# ppmacBoard.net
KiCad netlist of a schematic drawn in EAGLE
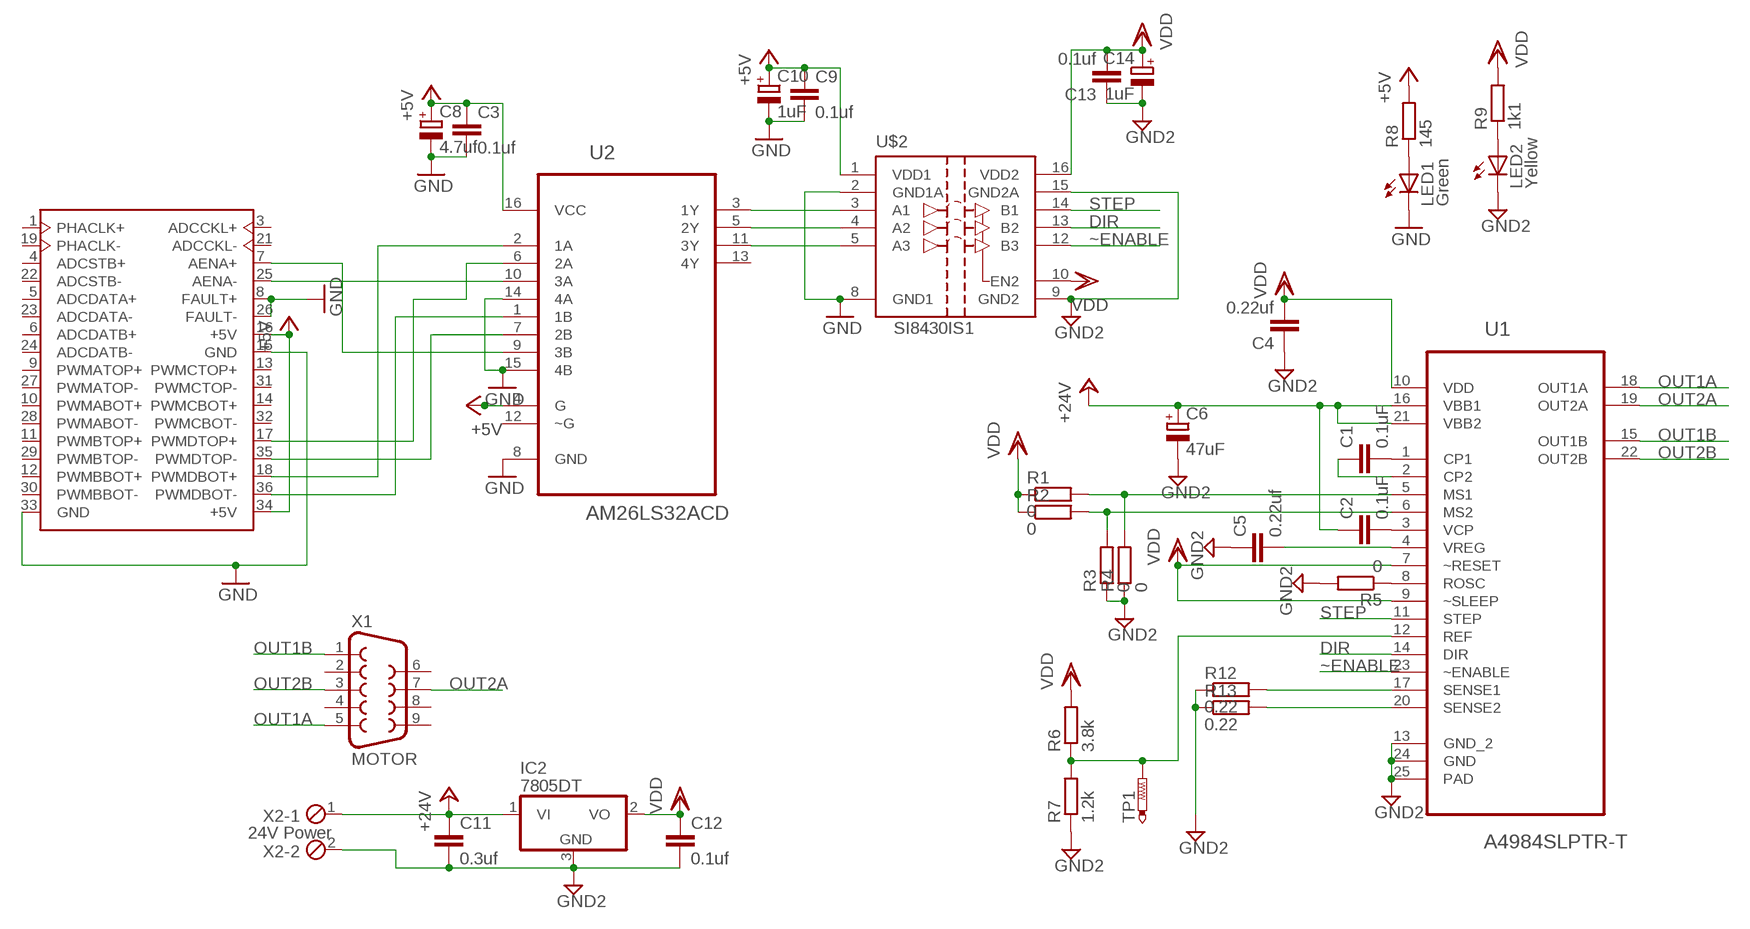
[diagram p0: schematic, sheet 1]

(export (version "E")
  (design (tool "Eeschema 10.0.6"))
  (components
    (comp (ref "C1")
      (value "0.1uF")
      (footprint "eagle-import:C1206")
      (fields (field (name "MPN") "MC1206B104K250CT") (field (name "PARTNO") "C1206C104K3RACTU"))
      (libsource (lib "eagle-import") (part "C-EUC1206"))
    )
    (comp (ref "C2")
      (value "0.1uF")
      (footprint "eagle-import:C1206")
      (fields (field (name "MPN") "MC1206B104K250CT") (field (name "PARTNO") "C1206C104K3RACTU"))
      (libsource (lib "eagle-import") (part "C-EUC1206"))
    )
    (comp (ref "C3")
      (value "0.1uf")
      (footprint "eagle-import:C1206")
      (fields (field (name "PARTNO") "C1206C104K3RACTU"))
      (libsource (lib "eagle-import") (part "C-EUC1206"))
    )
    (comp (ref "C4")
      (value "0.22uf")
      (footprint "eagle-import:C1206")
      (fields (field (name "PARTNO") "C1206C224K5RACTU"))
      (libsource (lib "eagle-import") (part "C-EUC1206"))
    )
    (comp (ref "C5")
      (value "0.22uf")
      (footprint "eagle-import:C1206")
      (fields (field (name "PARTNO") "C1206C224K5RACTU"))
      (libsource (lib "eagle-import") (part "C-EUC1206"))
    )
    (comp (ref "C6")
      (value "47uF")
      (footprint "eagle-import:E7,5-18")
      (fields (field (name "PARTNO") "ESH476M035AE3AA"))
      (libsource (lib "eagle-import") (part "CPOL-EUE7.5-18"))
    )
    (comp (ref "C8")
      (value "4.7uf")
      (footprint "eagle-import:A_3216-18W")
      (fields (field (name "PARTNO") "T491A475M025AT"))
      (libsource (lib "eagle-import") (part "CPOL-EUA/3216-18W"))
    )
    (comp (ref "C9")
      (value "0.1uf")
      (footprint "eagle-import:C1206")
      (fields (field (name "PARTNO") "C1206C104K3RACTU"))
      (libsource (lib "eagle-import") (part "C-EUC1206"))
    )
    (comp (ref "C10")
      (value "1uF")
      (footprint "eagle-import:A_3216-18W")
      (fields (field (name "PARTNO") "T491A105K025AT"))
      (libsource (lib "eagle-import") (part "CPOL-EUA/3216-18W"))
    )
    (comp (ref "C11")
      (value "0.3uf")
      (footprint "eagle-import:C1206")
      (fields (field (name "PARTNO") "C3216X7R1E334K"))
      (libsource (lib "eagle-import") (part "C-EUC1206"))
    )
    (comp (ref "C12")
      (value "0.1uf")
      (footprint "eagle-import:C1206")
      (fields (field (name "PARTNO") "C1206C104K3RACTU"))
      (libsource (lib "eagle-import") (part "C-EUC1206"))
    )
    (comp (ref "C13")
      (value "0.1uf")
      (footprint "eagle-import:C1206")
      (fields (field (name "PARTNO") "C1206C104K3RACTU"))
      (libsource (lib "eagle-import") (part "C-EUC1206"))
    )
    (comp (ref "C14")
      (value "1uF")
      (footprint "eagle-import:A_3216-18W")
      (fields (field (name "PARTNO") "T491A105K025AT"))
      (libsource (lib "eagle-import") (part "CPOL-EUA/3216-18W"))
    )
    (comp (ref "IC2")
      (value "7805DT")
      (footprint "eagle-import:TO252")
      (fields (field (name "PARTNO") "BA17805FP-E2"))
      (libsource (lib "eagle-import") (part "78DT05"))
    )
    (comp (ref "LED1")
      (value "Green")
      (footprint "eagle-import:1206")
      (fields (field (name "MPN") "KP-3216CGCK") (field (name "PARTNO") "LG N971-KN-1"))
      (libsource (lib "eagle-import") (part "LEDSMT1206"))
    )
    (comp (ref "LED2")
      (value "Yellow")
      (footprint "eagle-import:1206")
      (fields (field (name "MPN") "KP-3216SYCK") (field (name "PARTNO") "APT3216YC"))
      (libsource (lib "eagle-import") (part "LEDSMT1206"))
    )
    (comp (ref "R1")
      (value "0")
      (footprint "eagle-import:R1206")
      (fields (field (name "PARTNO") "RMCF1206ZT0R00"))
      (libsource (lib "eagle-import") (part "R-EU_R1206"))
    )
    (comp (ref "R2")
      (value "0")
      (footprint "eagle-import:R1206")
      (fields (field (name "PARTNO") "RMCF1206ZT0R00"))
      (libsource (lib "eagle-import") (part "R-EU_R1206"))
    )
    (comp (ref "R3")
      (value "0")
      (footprint "eagle-import:R1206")
      (fields (field (name "PARTNO") "RMCF1206ZT0R00"))
      (libsource (lib "eagle-import") (part "R-EU_R1206"))
    )
    (comp (ref "R4")
      (value "0")
      (footprint "eagle-import:R1206")
      (fields (field (name "PARTNO") "RMCF1206ZT0R00"))
      (libsource (lib "eagle-import") (part "R-EU_R1206"))
    )
    (comp (ref "R5")
      (value "0")
      (footprint "eagle-import:R1206")
      (fields (field (name "PARTNO") "RMCF1206ZT0R00"))
      (libsource (lib "eagle-import") (part "R-EU_R1206"))
    )
    (comp (ref "R6")
      (value "3.8k")
      (footprint "eagle-import:R1206")
      (fields (field (name "PARTNO") "RMCF1206FT3K83"))
      (libsource (lib "eagle-import") (part "R-EU_R1206"))
    )
    (comp (ref "R7")
      (value "1.2k")
      (footprint "eagle-import:R1206")
      (fields (field (name "PARTNO") "RC1206FR-071K2L"))
      (libsource (lib "eagle-import") (part "R-EU_R1206"))
    )
    (comp (ref "R8")
      (value "145")
      (footprint "eagle-import:R1206")
      (fields (field (name "PARTNO") "RC1206FR-07140RL"))
      (libsource (lib "eagle-import") (part "R-EU_R1206"))
    )
    (comp (ref "R9")
      (value "1k1")
      (footprint "eagle-import:R1206")
      (fields (field (name "PARTNO") "RC1206FR-071K1L"))
      (libsource (lib "eagle-import") (part "R-EU_R1206"))
    )
    (comp (ref "R12")
      (value "0.22")
      (footprint "eagle-import:R2010")
      (fields (field (name "PARTNO") "WSLT2010R2200FEB18"))
      (libsource (lib "eagle-import") (part "R-EU_R2010"))
    )
    (comp (ref "R13")
      (value "0.22")
      (footprint "eagle-import:R2010")
      (fields (field (name "PARTNO") "WSLT2010R2200FEB18"))
      (libsource (lib "eagle-import") (part "R-EU_R2010"))
    )
    (comp (ref "TP1")
      (value "PTR1PAD1-13")
      (footprint "eagle-import:P1-13")
      (libsource (lib "eagle-import") (part "PTR1PAD1-13"))
    )
    (comp (ref "U$1")
      (value "DIGAMPOUT_PCB")
      (footprint "eagle-import:3M_10136-52B2PC_PCB")
      (fields (field (name "PARTNO") "10136-3000PE"))
      (libsource (lib "eagle-import") (part "DIGAMPOUT_PCB"))
    )
    (comp (ref "U$2")
      (value "SI8430IS1")
      (footprint "eagle-import:SO16")
      (fields (field (name "PARTNO") "SI8430AB-D-IS1"))
      (libsource (lib "eagle-import") (part "SI8430IS1"))
    )
    (comp (ref "U1")
      (value "A4984SLPTR-T")
      (footprint "eagle-import:SOP65P640X120-24N")
      (libsource (lib "eagle-import") (part "A4984SLPTR-T"))
    )
    (comp (ref "U2")
      (value "AM26LS32ACD")
      (footprint "eagle-import:SOIC127P600X175-16N")
      (fields (field (name "MF") "TEXAS INSTRUMENTS") (field (name "PARTNO") "AM26LS32ACDR"))
      (libsource (lib "eagle-import") (part "AM26LS32ACD"))
    )
    (comp (ref "X1")
      (value "MOTOR")
      (footprint "eagle-import:F09H")
      (fields (field (name "PARTNO") "DLS1XS5AK40X"))
      (libsource (lib "eagle-import") (part "F09H"))
    )
    (comp (ref "X2")
      (value "24V Power")
      (footprint "eagle-import:2POL254")
      (fields (field (name "PARTNO") "OSTTE020104"))
      (libsource (lib "eagle-import") (part "MPT2"))
    )
  )
  (nets
    (net (code "1") (name "+5V") (class "Default")
      (node (ref "C10") (pin "+") (pinfunction "+_+") (pintype "passive"))
      (node (ref "C3") (pin "1") (pinfunction "1_1") (pintype "passive"))
      (node (ref "C8") (pin "+") (pinfunction "+_+") (pintype "passive"))
      (node (ref "C9") (pin "1") (pinfunction "1_1") (pintype "passive"))
      (node (ref "R8") (pin "2") (pinfunction "2_2") (pintype "passive"))
      (node (ref "U$1") (pin "16") (pinfunction "+5V_16") (pintype "power_in"))
      (node (ref "U$1") (pin "34") (pinfunction "+5V_34") (pintype "power_in"))
      (node (ref "U$2") (pin "1") (pinfunction "VDD1_1") (pintype "power_in"))
      (node (ref "U2") (pin "16") (pinfunction "VCC_16") (pintype "power_in"))
      (node (ref "U2") (pin "4") (pinfunction "G_4") (pintype "input"))
    )
    (net (code "2") (name "+24V") (class "Default")
      (node (ref "C11") (pin "1") (pinfunction "1_1") (pintype "passive"))
      (node (ref "C2") (pin "1") (pinfunction "1_1") (pintype "passive"))
      (node (ref "C6") (pin "+") (pinfunction "+_+") (pintype "passive"))
      (node (ref "IC2") (pin "1") (pinfunction "VI_1") (pintype "input"))
      (node (ref "U1") (pin "16") (pinfunction "VBB1_16") (pintype "power_in"))
      (node (ref "U1") (pin "21") (pinfunction "VBB2_21") (pintype "power_in"))
      (node (ref "X2") (pin "1") (pinfunction "1_1") (pintype "passive"))
    )
    (net (code "3") (name "/DIR") (class "Default")
      (node (ref "U$2") (pin "13") (pinfunction "B2_13") (pintype "output"))
      (node (ref "U1") (pin "14") (pinfunction "DIR_14") (pintype "input"))
    )
    (net (code "4") (name "/OUT1A") (class "Default")
      (node (ref "U1") (pin "18") (pinfunction "OUT1A_18") (pintype "output"))
      (node (ref "X1") (pin "5") (pinfunction "5_5") (pintype "passive"))
    )
    (net (code "5") (name "/OUT1B") (class "Default")
      (node (ref "U1") (pin "15") (pinfunction "OUT1B_15") (pintype "output"))
      (node (ref "X1") (pin "1") (pinfunction "1_1") (pintype "passive"))
    )
    (net (code "6") (name "/OUT2A") (class "Default")
      (node (ref "U1") (pin "19") (pinfunction "OUT2A_19") (pintype "output"))
      (node (ref "X1") (pin "7") (pinfunction "7_7") (pintype "passive"))
    )
    (net (code "7") (name "/OUT2B") (class "Default")
      (node (ref "U1") (pin "22") (pinfunction "OUT2B_22") (pintype "output"))
      (node (ref "X1") (pin "3") (pinfunction "3_3") (pintype "passive"))
    )
    (net (code "8") (name "/STEP") (class "Default")
      (node (ref "U$2") (pin "14") (pinfunction "B1_14") (pintype "output"))
      (node (ref "U1") (pin "11") (pinfunction "STEP_11") (pintype "input"))
    )
    (net (code "9") (name "/~{ENABLE}") (class "Default")
      (node (ref "U$2") (pin "12") (pinfunction "B3_12") (pintype "output"))
      (node (ref "U1") (pin "23") (pinfunction "~{ENABLE}_23") (pintype "input"))
    )
    (net (code "10") (name "GND") (class "Default")
      (node (ref "C10") (pin "-") (pinfunction "-_-") (pintype "passive"))
      (node (ref "C3") (pin "2") (pinfunction "2_2") (pintype "passive"))
      (node (ref "C8") (pin "-") (pinfunction "-_-") (pintype "passive"))
      (node (ref "C9") (pin "2") (pinfunction "2_2") (pintype "passive"))
      (node (ref "LED1") (pin "C") (pinfunction "C_C") (pintype "passive"))
      (node (ref "U$1") (pin "15") (pinfunction "GND_15") (pintype "power_in"))
      (node (ref "U$1") (pin "26") (pinfunction "FAULT-_26") (pintype "input"))
      (node (ref "U$1") (pin "33") (pinfunction "GND_33") (pintype "power_in"))
      (node (ref "U$1") (pin "8") (pinfunction "FAULT+_8") (pintype "input"))
      (node (ref "U$2") (pin "2") (pinfunction "GND1A_2") (pintype "power_in"))
      (node (ref "U$2") (pin "8") (pinfunction "GND1_8") (pintype "power_in"))
      (node (ref "U2") (pin "14") (pinfunction "4A_14") (pintype "input"))
      (node (ref "U2") (pin "15") (pinfunction "4B_15") (pintype "input"))
      (node (ref "U2") (pin "8") (pinfunction "GND_8") (pintype "passive"))
    )
    (net (code "11") (name "GND2") (class "Default")
      (node (ref "C11") (pin "2") (pinfunction "2_2") (pintype "passive"))
      (node (ref "C12") (pin "2") (pinfunction "2_2") (pintype "passive"))
      (node (ref "C13") (pin "1") (pinfunction "1_1") (pintype "passive"))
      (node (ref "C14") (pin "-") (pinfunction "-_-") (pintype "passive"))
      (node (ref "C4") (pin "1") (pinfunction "1_1") (pintype "passive"))
      (node (ref "C5") (pin "1") (pinfunction "1_1") (pintype "passive"))
      (node (ref "C6") (pin "-") (pinfunction "-_-") (pintype "passive"))
      (node (ref "IC2") (pin "3") (pinfunction "GND_3") (pintype "passive"))
      (node (ref "LED2") (pin "C") (pinfunction "C_C") (pintype "passive"))
      (node (ref "R12") (pin "1") (pinfunction "1_1") (pintype "passive"))
      (node (ref "R13") (pin "1") (pinfunction "1_1") (pintype "passive"))
      (node (ref "R3") (pin "1") (pinfunction "1_1") (pintype "passive"))
      (node (ref "R4") (pin "1") (pinfunction "1_1") (pintype "passive"))
      (node (ref "R5") (pin "2") (pinfunction "2_2") (pintype "passive"))
      (node (ref "R7") (pin "1") (pinfunction "1_1") (pintype "passive"))
      (node (ref "U$2") (pin "15") (pinfunction "GND2A_15") (pintype "power_in"))
      (node (ref "U$2") (pin "9") (pinfunction "GND2_9") (pintype "power_in"))
      (node (ref "U1") (pin "13") (pinfunction "GND_2_13") (pintype "passive"))
      (node (ref "U1") (pin "24") (pinfunction "GND_24") (pintype "passive"))
      (node (ref "U1") (pin "25") (pinfunction "PAD_25") (pintype "passive"))
      (node (ref "X2") (pin "2") (pinfunction "1_2") (pintype "passive"))
    )
    (net (code "12") (name "Net-(LED1-PadA)") (class "Default")
      (node (ref "LED1") (pin "A") (pinfunction "A_A") (pintype "passive"))
      (node (ref "R8") (pin "1") (pinfunction "1_1") (pintype "passive"))
    )
    (net (code "13") (name "Net-(LED2-PadA)") (class "Default")
      (node (ref "LED2") (pin "A") (pinfunction "A_A") (pintype "passive"))
      (node (ref "R9") (pin "1") (pinfunction "1_1") (pintype "passive"))
    )
    (net (code "14") (name "Net-(U$1-AENA+)") (class "Default")
      (node (ref "U$1") (pin "7") (pinfunction "AENA+_7") (pintype "output"))
      (node (ref "U2") (pin "9") (pinfunction "3B_9") (pintype "input"))
    )
    (net (code "15") (name "Net-(U$1-AENA-)") (class "Default")
      (node (ref "U$1") (pin "25") (pinfunction "AENA-_25") (pintype "output"))
      (node (ref "U2") (pin "10") (pinfunction "3A_10") (pintype "input"))
    )
    (net (code "16") (name "Net-(U$1-PWMDBOT+)") (class "Default")
      (node (ref "U$1") (pin "18") (pinfunction "PWMDBOT+_18") (pintype "output"))
      (node (ref "U2") (pin "2") (pinfunction "1A_2") (pintype "input"))
    )
    (net (code "17") (name "Net-(U$1-PWMDBOT-)") (class "Default")
      (node (ref "U$1") (pin "36") (pinfunction "PWMDBOT-_36") (pintype "output"))
      (node (ref "U2") (pin "1") (pinfunction "1B_1") (pintype "input"))
    )
    (net (code "18") (name "Net-(U$1-PWMDTOP+)") (class "Default")
      (node (ref "U$1") (pin "17") (pinfunction "PWMDTOP+_17") (pintype "output"))
      (node (ref "U2") (pin "6") (pinfunction "2A_6") (pintype "input"))
    )
    (net (code "19") (name "Net-(U$1-PWMDTOP-)") (class "Default")
      (node (ref "U$1") (pin "35") (pinfunction "PWMDTOP-_35") (pintype "output"))
      (node (ref "U2") (pin "7") (pinfunction "2B_7") (pintype "input"))
    )
    (net (code "20") (name "Net-(U$2-A1)") (class "Default")
      (node (ref "U$2") (pin "3") (pinfunction "A1_3") (pintype "input"))
      (node (ref "U2") (pin "3") (pinfunction "1Y_3") (pintype "output"))
    )
    (net (code "21") (name "Net-(U$2-A2)") (class "Default")
      (node (ref "U$2") (pin "4") (pinfunction "A2_4") (pintype "input"))
      (node (ref "U2") (pin "5") (pinfunction "2Y_5") (pintype "output"))
    )
    (net (code "22") (name "Net-(U$2-A3)") (class "Default")
      (node (ref "U$2") (pin "5") (pinfunction "A3_5") (pintype "input"))
      (node (ref "U2") (pin "11") (pinfunction "3Y_11") (pintype "output"))
    )
    (net (code "23") (name "Net-(U1-CP1)") (class "Default")
      (node (ref "C1") (pin "2") (pinfunction "2_2") (pintype "passive"))
      (node (ref "U1") (pin "1") (pinfunction "CP1_1") (pintype "passive"))
    )
    (net (code "24") (name "Net-(U1-CP2)") (class "Default")
      (node (ref "C1") (pin "1") (pinfunction "1_1") (pintype "passive"))
      (node (ref "U1") (pin "2") (pinfunction "CP2_2") (pintype "passive"))
    )
    (net (code "25") (name "Net-(U1-MS1)") (class "Default")
      (node (ref "R1") (pin "2") (pinfunction "2_2") (pintype "passive"))
      (node (ref "R4") (pin "2") (pinfunction "2_2") (pintype "passive"))
      (node (ref "U1") (pin "5") (pinfunction "MS1_5") (pintype "input"))
    )
    (net (code "26") (name "Net-(U1-MS2)") (class "Default")
      (node (ref "R2") (pin "2") (pinfunction "2_2") (pintype "passive"))
      (node (ref "R3") (pin "2") (pinfunction "2_2") (pintype "passive"))
      (node (ref "U1") (pin "6") (pinfunction "MS2_6") (pintype "input"))
    )
    (net (code "27") (name "Net-(U1-REF)") (class "Default")
      (node (ref "R6") (pin "1") (pinfunction "1_1") (pintype "passive"))
      (node (ref "R7") (pin "2") (pinfunction "2_2") (pintype "passive"))
      (node (ref "TP1") (pin "TP") (pinfunction "TP_TP") (pintype "input"))
      (node (ref "U1") (pin "12") (pinfunction "REF_12") (pintype "input"))
    )
    (net (code "28") (name "Net-(U1-ROSC)") (class "Default")
      (node (ref "R5") (pin "1") (pinfunction "1_1") (pintype "passive"))
      (node (ref "U1") (pin "8") (pinfunction "ROSC_8") (pintype "input"))
    )
    (net (code "29") (name "Net-(U1-SENSE1)") (class "Default")
      (node (ref "R12") (pin "2") (pinfunction "2_2") (pintype "passive"))
      (node (ref "U1") (pin "17") (pinfunction "SENSE1_17") (pintype "input"))
    )
    (net (code "30") (name "Net-(U1-SENSE2)") (class "Default")
      (node (ref "R13") (pin "2") (pinfunction "2_2") (pintype "passive"))
      (node (ref "U1") (pin "20") (pinfunction "SENSE2_20") (pintype "input"))
    )
    (net (code "31") (name "Net-(U1-VCP)") (class "Default")
      (node (ref "C2") (pin "2") (pinfunction "2_2") (pintype "passive"))
      (node (ref "U1") (pin "3") (pinfunction "VCP_3") (pintype "passive"))
    )
    (net (code "32") (name "Net-(U1-VREG)") (class "Default")
      (node (ref "C5") (pin "2") (pinfunction "2_2") (pintype "passive"))
      (node (ref "U1") (pin "4") (pinfunction "VREG_4") (pintype "passive"))
    )
    (net (code "33") (name "VDD") (class "Default")
      (node (ref "C12") (pin "1") (pinfunction "1_1") (pintype "passive"))
      (node (ref "C13") (pin "2") (pinfunction "2_2") (pintype "passive"))
      (node (ref "C14") (pin "+") (pinfunction "+_+") (pintype "passive"))
      (node (ref "C4") (pin "2") (pinfunction "2_2") (pintype "passive"))
      (node (ref "IC2") (pin "2") (pinfunction "VO_2") (pintype "passive"))
      (node (ref "R1") (pin "1") (pinfunction "1_1") (pintype "passive"))
      (node (ref "R2") (pin "1") (pinfunction "1_1") (pintype "passive"))
      (node (ref "R6") (pin "2") (pinfunction "2_2") (pintype "passive"))
      (node (ref "R9") (pin "2") (pinfunction "2_2") (pintype "passive"))
      (node (ref "U$2") (pin "10") (pinfunction "EN2_10") (pintype "input"))
      (node (ref "U$2") (pin "16") (pinfunction "VDD2_16") (pintype "power_in"))
      (node (ref "U1") (pin "10") (pinfunction "VDD_10") (pintype "power_in"))
      (node (ref "U1") (pin "7") (pinfunction "~{RESET}_7") (pintype "input"))
      (node (ref "U1") (pin "9") (pinfunction "~{SLEEP}_9") (pintype "input"))
    )
    (net (code "34") (name "unconnected-(U$1-ADCCKL+-Pad3)") (class "Default")
      (node (ref "U$1") (pin "3") (pinfunction "ADCCKL+_3") (pintype "output"))
    )
    (net (code "35") (name "unconnected-(U$1-ADCCKL--Pad21)") (class "Default")
      (node (ref "U$1") (pin "21") (pinfunction "ADCCKL-_21") (pintype "output"))
    )
    (net (code "36") (name "unconnected-(U$1-ADCDATA+-Pad5)") (class "Default")
      (node (ref "U$1") (pin "5") (pinfunction "ADCDATA+_5") (pintype "input"))
    )
    (net (code "37") (name "unconnected-(U$1-ADCDATA--Pad23)") (class "Default")
      (node (ref "U$1") (pin "23") (pinfunction "ADCDATA-_23") (pintype "input"))
    )
    (net (code "38") (name "unconnected-(U$1-ADCDATB+-Pad6)") (class "Default")
      (node (ref "U$1") (pin "6") (pinfunction "ADCDATB+_6") (pintype "input"))
    )
    (net (code "39") (name "unconnected-(U$1-ADCDATB--Pad24)") (class "Default")
      (node (ref "U$1") (pin "24") (pinfunction "ADCDATB-_24") (pintype "input"))
    )
    (net (code "40") (name "unconnected-(U$1-ADCSTB+-Pad4)") (class "Default")
      (node (ref "U$1") (pin "4") (pinfunction "ADCSTB+_4") (pintype "output"))
    )
    (net (code "41") (name "unconnected-(U$1-ADCSTB--Pad22)") (class "Default")
      (node (ref "U$1") (pin "22") (pinfunction "ADCSTB-_22") (pintype "output"))
    )
    (net (code "42") (name "unconnected-(U$1-PHACLK+-Pad1)") (class "Default")
      (node (ref "U$1") (pin "1") (pinfunction "PHACLK+_1") (pintype "output"))
    )
    (net (code "43") (name "unconnected-(U$1-PHACLK--Pad19)") (class "Default")
      (node (ref "U$1") (pin "19") (pinfunction "PHACLK-_19") (pintype "output"))
    )
    (net (code "44") (name "unconnected-(U$1-PWMABOT+-Pad10)") (class "Default")
      (node (ref "U$1") (pin "10") (pinfunction "PWMABOT+_10") (pintype "output"))
    )
    (net (code "45") (name "unconnected-(U$1-PWMABOT--Pad28)") (class "Default")
      (node (ref "U$1") (pin "28") (pinfunction "PWMABOT-_28") (pintype "output"))
    )
    (net (code "46") (name "unconnected-(U$1-PWMATOP+-Pad9)") (class "Default")
      (node (ref "U$1") (pin "9") (pinfunction "PWMATOP+_9") (pintype "output"))
    )
    (net (code "47") (name "unconnected-(U$1-PWMATOP--Pad27)") (class "Default")
      (node (ref "U$1") (pin "27") (pinfunction "PWMATOP-_27") (pintype "output"))
    )
    (net (code "48") (name "unconnected-(U$1-PWMBBOT+-Pad12)") (class "Default")
      (node (ref "U$1") (pin "12") (pinfunction "PWMBBOT+_12") (pintype "output"))
    )
    (net (code "49") (name "unconnected-(U$1-PWMBBOT--Pad30)") (class "Default")
      (node (ref "U$1") (pin "30") (pinfunction "PWMBBOT-_30") (pintype "output"))
    )
    (net (code "50") (name "unconnected-(U$1-PWMBTOP+-Pad11)") (class "Default")
      (node (ref "U$1") (pin "11") (pinfunction "PWMBTOP+_11") (pintype "output"))
    )
    (net (code "51") (name "unconnected-(U$1-PWMBTOP--Pad29)") (class "Default")
      (node (ref "U$1") (pin "29") (pinfunction "PWMBTOP-_29") (pintype "output"))
    )
    (net (code "52") (name "unconnected-(U$1-PWMCBOT+-Pad14)") (class "Default")
      (node (ref "U$1") (pin "14") (pinfunction "PWMCBOT+_14") (pintype "output"))
    )
    (net (code "53") (name "unconnected-(U$1-PWMCBOT--Pad32)") (class "Default")
      (node (ref "U$1") (pin "32") (pinfunction "PWMCBOT-_32") (pintype "output"))
    )
    (net (code "54") (name "unconnected-(U$1-PWMCTOP+-Pad13)") (class "Default")
      (node (ref "U$1") (pin "13") (pinfunction "PWMCTOP+_13") (pintype "output"))
    )
    (net (code "55") (name "unconnected-(U$1-PWMCTOP--Pad31)") (class "Default")
      (node (ref "U$1") (pin "31") (pinfunction "PWMCTOP-_31") (pintype "output"))
    )
    (net (code "56") (name "unconnected-(U2-4Y-Pad13)") (class "Default")
      (node (ref "U2") (pin "13") (pinfunction "4Y_13") (pintype "output"))
    )
    (net (code "57") (name "unconnected-(U2-~{G}-Pad12)") (class "Default")
      (node (ref "U2") (pin "12") (pinfunction "~{G}_12") (pintype "input"))
    )
    (net (code "58") (name "unconnected-(X1-Pad2)") (class "Default")
      (node (ref "X1") (pin "2") (pinfunction "2_2") (pintype "passive"))
    )
    (net (code "59") (name "unconnected-(X1-Pad4)") (class "Default")
      (node (ref "X1") (pin "4") (pinfunction "4_4") (pintype "passive"))
    )
    (net (code "60") (name "unconnected-(X1-Pad6)") (class "Default")
      (node (ref "X1") (pin "6") (pinfunction "6_6") (pintype "passive"))
    )
    (net (code "61") (name "unconnected-(X1-Pad8)") (class "Default")
      (node (ref "X1") (pin "8") (pinfunction "8_8") (pintype "passive"))
    )
    (net (code "62") (name "unconnected-(X1-Pad9)") (class "Default")
      (node (ref "X1") (pin "9") (pinfunction "9_9") (pintype "passive"))
    )
  )
)
